# 1_P1.net
KiCad netlist of a schematic drawn in Altium Designer
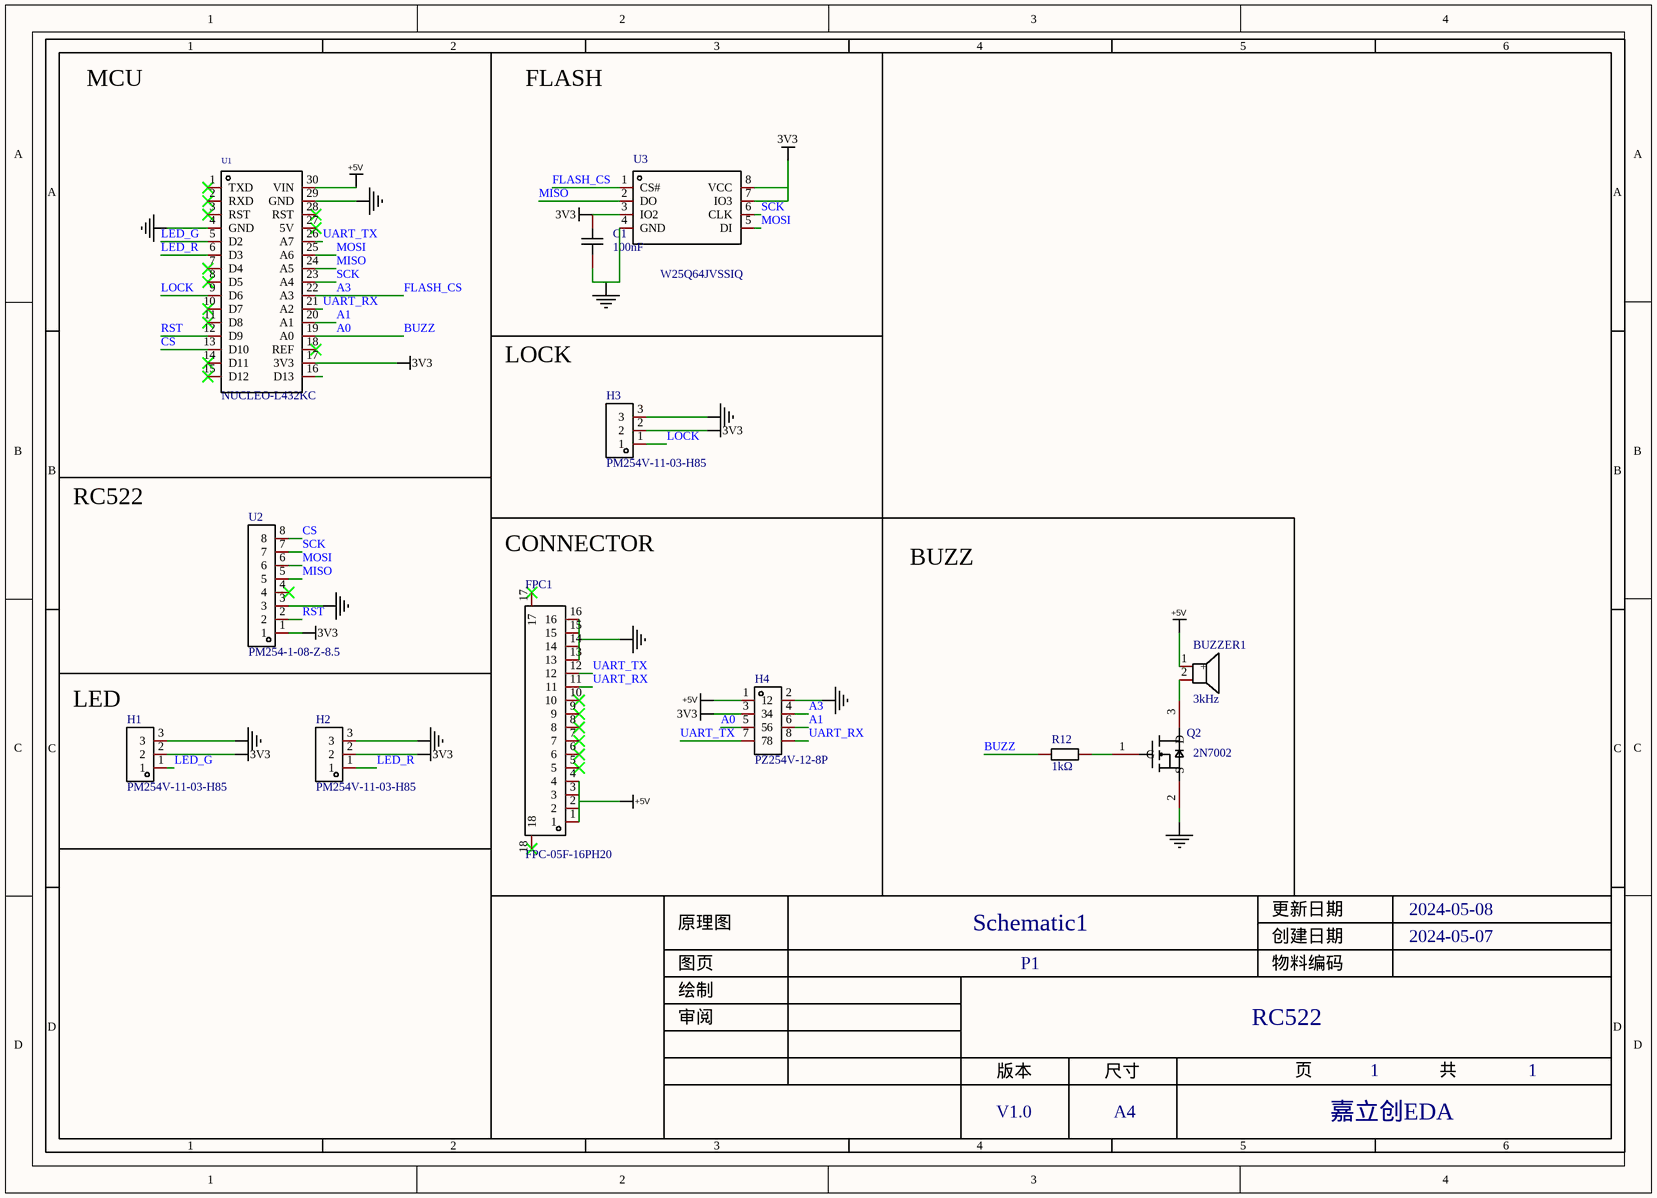
[diagram p0: 1_P1.schdoc]

(export (version "E")
  (design (tool "Eeschema 10.0.6"))
  (components
    (comp (ref "BUZZER1")
      (value "3kHz")
      (description "驱动方式:有源(内含驱动线路);构造类型:电磁式;频率:3kHz;声压(SPL):85dB@5V,10cm;")
      (fields
        (field (name "NAME") "3kHz")
        (field (name "MANUFACTURER") "华能")
        (field (name "MANUFACTURER PART") "HNB09A05")
      )
      (libsource (lib "altium-import") (part "root_0_HNB09A05_"))
    )
    (comp (ref "C1")
      (value "100nF")
      (description "容值:100nF;精度:±10%;额定电压:50V;材质(温度系数):X7R;")
      (fields
        (field (name "NAME") "100nF")
        (field (name "MANUFACTURER") "YAGEO(国巨)")
        (field (name "MANUFACTURER PART") "CC0603KRX7R9BB104")
      )
      (libsource (lib "altium-import") (part "root_1_CC0603KRX7R9BB104_"))
    )
    (comp (ref "FPC1")
      (value "FPC-05F-16PH20")
      (description "锁定特性:翻盖式;触点类型:下接;触点数量:16P;间距:0.5mm;安装类型:卧贴;工作温度范围:-25℃~+85℃;")
      (fields (field (name "NAME") "FPC-05F-16PH20") (field (name "MANUFACTURER") "XUNPU(讯普)"))
      (libsource (lib "altium-import") (part "root_2_FPC-05F-16PH20_"))
    )
    (comp (ref "H1")
      (value "PM254V-11-03-H85")
      (description "插孔结构:1x3P;间距:2.54mm;行距:-;安装类型:直插;排数:单排;总孔位数:3P;塑高:-;触头材质:黄铜;触头镀层:-;")
      (fields (field (name "NAME") "PM254V-11-03-H85") (field (name "MANUFACTURER") "XFCN(兴飞)"))
      (libsource (lib "altium-import") (part "root_2_PM254V-11-03-H85_"))
    )
    (comp (ref "H2")
      (value "PM254V-11-03-H85")
      (description "插孔结构:1x3P;间距:2.54mm;行距:-;安装类型:直插;排数:单排;总孔位数:3P;塑高:-;触头材质:黄铜;触头镀层:-;")
      (fields (field (name "NAME") "PM254V-11-03-H85") (field (name "MANUFACTURER") "XFCN(兴飞)"))
      (libsource (lib "altium-import") (part "root_2_PM254V-11-03-H85_"))
    )
    (comp (ref "H3")
      (value "PM254V-11-03-H85")
      (description "插孔结构:1x3P;间距:2.54mm;行距:-;安装类型:直插;排数:单排;总孔位数:3P;塑高:-;触头材质:黄铜;触头镀层:-;")
      (fields (field (name "NAME") "PM254V-11-03-H85") (field (name "MANUFACTURER") "XFCN(兴飞)"))
      (libsource (lib "altium-import") (part "root_2_PM254V-11-03-H85_"))
    )
    (comp (ref "H4")
      (value "PZ254V-12-8P")
      (fields (field (name "NAME") "PZ254V-12-8P") (field (name "MANUFACTURER") "XFCN(兴飞)"))
      (libsource (lib "altium-import") (part "root_0_PZ254V-12-8P_"))
    )
    (comp (ref "Q2")
      (value "2N7002")
      (fields (field (name "NAME") "2N7002") (field (name "MANUFACTURER") "JSMSEMI(杰盛微)"))
      (libsource (lib "altium-import") (part "root_0_2N7002_C916396_"))
    )
    (comp (ref "R12")
      (value "1kΩ")
      (description "电阻类型:厚膜电阻;阻值:1kΩ;精度:±1%;功率:100mW;最大工作电压:75V;温度系数:±100ppm/℃;")
      (fields
        (field (name "NAME") "1kΩ")
        (field (name "MANUFACTURER") "YAGEO(国巨)")
        (field (name "MANUFACTURER PART") "RC0603FR-071KL")
      )
      (libsource (lib "altium-import") (part "root_2_RC0603FR-071KL_"))
    )
    (comp (ref "U1")
      (value "NUCLEO-L432KC")
      (description "处理器:-;运行内存:-;USB:-;WIFI协议:-;蓝牙:-;以太网:-;")
      (fields (field (name "NAME") "NUCLEO-L432KC") (field (name "MANUFACTURER") "ST(意法半导体)"))
      (libsource (lib "altium-import") (part "root_0_NUCLEO-L432KC_"))
    )
    (comp (ref "U2")
      (value "PM254-1-08-Z-8.5")
      (fields (field (name "NAME") "PM254-1-08-Z-8.5") (field (name "MANUFACTURER") "HCTL(华灿天禄)"))
      (libsource (lib "altium-import") (part "root_2_PM254-1-08-Z-8.5_"))
    )
    (comp (ref "U3")
      (value "W25Q64JVSSIQ")
      (description "64M-bit/8M-byte FLASH芯片,SPI接口 133MHz(266/532MHz Dual/Quad-SPI) 比W25Q64FVSSIG更高速度")
      (fields (field (name "NAME") "W25Q64JVSSIQ") (field (name "MANUFACTURER") "WINBOND(华邦)"))
      (libsource (lib "altium-import") (part "root_0_W25Q64JVSSIQ_C83140_"))
    )
  )
  (nets
    (net (code "1") (name "+5V") (class "Default")
      (node (ref "BUZZER1") (pin "1") (pinfunction "+_1") (pintype "passive"))
      (node (ref "FPC1") (pin "1") (pinfunction "1_1") (pintype "passive"))
      (node (ref "FPC1") (pin "2") (pinfunction "2_2") (pintype "passive"))
      (node (ref "FPC1") (pin "3") (pinfunction "3_3") (pintype "passive"))
      (node (ref "FPC1") (pin "4") (pinfunction "4_4") (pintype "passive"))
      (node (ref "H4") (pin "1") (pinfunction "1_1") (pintype "passive"))
      (node (ref "U1") (pin "30") (pinfunction "VIN_30") (pintype "passive"))
    )
    (net (code "2") (name "/A0") (class "Default")
      (node (ref "H4") (pin "5") (pinfunction "5_5") (pintype "passive"))
      (node (ref "R12") (pin "2") (pinfunction "2_2") (pintype "passive"))
      (node (ref "U1") (pin "19") (pinfunction "A0_19") (pintype "passive"))
    )
    (net (code "3") (name "/A1") (class "Default")
      (node (ref "H4") (pin "6") (pinfunction "6_6") (pintype "passive"))
      (node (ref "U1") (pin "20") (pinfunction "A1_20") (pintype "passive"))
    )
    (net (code "4") (name "/A3") (class "Default")
      (node (ref "H4") (pin "4") (pinfunction "4_4") (pintype "passive"))
      (node (ref "U1") (pin "22") (pinfunction "A3_22") (pintype "passive"))
      (node (ref "U3") (pin "1") (pinfunction "CS#_1") (pintype "passive"))
    )
    (net (code "5") (name "/CS") (class "Default")
      (node (ref "U1") (pin "13") (pinfunction "D10_13") (pintype "passive"))
      (node (ref "U2") (pin "8") (pinfunction "8_8") (pintype "passive"))
    )
    (net (code "6") (name "/LED_G") (class "Default")
      (node (ref "H1") (pin "1") (pinfunction "1_1") (pintype "passive"))
      (node (ref "U1") (pin "5") (pinfunction "D2_5") (pintype "passive"))
    )
    (net (code "7") (name "/LED_R") (class "Default")
      (node (ref "H2") (pin "1") (pinfunction "1_1") (pintype "passive"))
      (node (ref "U1") (pin "6") (pinfunction "D3_6") (pintype "passive"))
    )
    (net (code "8") (name "/LOCK") (class "Default")
      (node (ref "H3") (pin "1") (pinfunction "1_1") (pintype "passive"))
      (node (ref "U1") (pin "9") (pinfunction "D6_9") (pintype "passive"))
    )
    (net (code "9") (name "/MISO") (class "Default")
      (node (ref "U1") (pin "24") (pinfunction "A5_24") (pintype "passive"))
      (node (ref "U2") (pin "5") (pinfunction "5_5") (pintype "passive"))
      (node (ref "U3") (pin "2") (pinfunction "DO_2") (pintype "passive"))
    )
    (net (code "10") (name "/MOSI") (class "Default")
      (node (ref "U1") (pin "25") (pinfunction "A6_25") (pintype "passive"))
      (node (ref "U2") (pin "6") (pinfunction "6_6") (pintype "passive"))
      (node (ref "U3") (pin "5") (pinfunction "DI_5") (pintype "passive"))
    )
    (net (code "11") (name "/RST") (class "Default")
      (node (ref "U1") (pin "12") (pinfunction "D9_12") (pintype "passive"))
      (node (ref "U2") (pin "2") (pinfunction "2_2") (pintype "passive"))
    )
    (net (code "12") (name "/SCK") (class "Default")
      (node (ref "U1") (pin "23") (pinfunction "A4_23") (pintype "passive"))
      (node (ref "U2") (pin "7") (pinfunction "7_7") (pintype "passive"))
      (node (ref "U3") (pin "6") (pinfunction "CLK_6") (pintype "passive"))
    )
    (net (code "13") (name "/UART_RX") (class "Default")
      (node (ref "FPC1") (pin "11") (pinfunction "11_11") (pintype "passive"))
      (node (ref "H4") (pin "8") (pinfunction "8_8") (pintype "passive"))
      (node (ref "U1") (pin "21") (pinfunction "A2_21") (pintype "passive"))
    )
    (net (code "14") (name "/UART_TX") (class "Default")
      (node (ref "FPC1") (pin "12") (pinfunction "12_12") (pintype "passive"))
      (node (ref "H4") (pin "7") (pinfunction "7_7") (pintype "passive"))
      (node (ref "U1") (pin "26") (pinfunction "A7_26") (pintype "passive"))
    )
    (net (code "15") (name "3V3") (class "Default")
      (node (ref "C1") (pin "2") (pinfunction "2_2") (pintype "passive"))
      (node (ref "H1") (pin "2") (pinfunction "2_2") (pintype "passive"))
      (node (ref "H2") (pin "2") (pinfunction "2_2") (pintype "passive"))
      (node (ref "H3") (pin "2") (pinfunction "2_2") (pintype "passive"))
      (node (ref "H4") (pin "3") (pinfunction "3_3") (pintype "passive"))
      (node (ref "U1") (pin "17") (pinfunction "3V3_17") (pintype "passive"))
      (node (ref "U2") (pin "1") (pinfunction "1_1") (pintype "passive"))
      (node (ref "U3") (pin "3") (pinfunction "IO2_3") (pintype "passive"))
      (node (ref "U3") (pin "7") (pinfunction "IO3_7") (pintype "passive"))
      (node (ref "U3") (pin "8") (pinfunction "VCC_8") (pintype "passive"))
    )
    (net (code "16") (name "<NO NET>") (class "Default")
      (node (ref "C1") (pin "1") (pinfunction "1_1") (pintype "passive"))
      (node (ref "FPC1") (pin "13") (pinfunction "13_13") (pintype "passive"))
      (node (ref "FPC1") (pin "14") (pinfunction "14_14") (pintype "passive"))
      (node (ref "FPC1") (pin "15") (pinfunction "15_15") (pintype "passive"))
      (node (ref "FPC1") (pin "16") (pinfunction "16_16") (pintype "passive"))
      (node (ref "H1") (pin "3") (pinfunction "3_3") (pintype "passive"))
      (node (ref "H2") (pin "3") (pinfunction "3_3") (pintype "passive"))
      (node (ref "H3") (pin "3") (pinfunction "3_3") (pintype "passive"))
      (node (ref "H4") (pin "2") (pinfunction "2_2") (pintype "passive"))
      (node (ref "Q2") (pin "2") (pinfunction "S_2") (pintype "passive"))
      (node (ref "U1") (pin "29") (pinfunction "GND_29") (pintype "passive"))
      (node (ref "U1") (pin "4") (pinfunction "GND_4") (pintype "passive"))
      (node (ref "U2") (pin "3") (pinfunction "3_3") (pintype "passive"))
      (node (ref "U3") (pin "4") (pinfunction "GND_4") (pintype "passive"))
    )
    (net (code "17") (name "Net-(Q2-D)") (class "Default")
      (node (ref "BUZZER1") (pin "2") (pinfunction "2_2") (pintype "passive"))
      (node (ref "Q2") (pin "3") (pinfunction "D_3") (pintype "passive"))
    )
    (net (code "18") (name "Net-(Q2-G)") (class "Default")
      (node (ref "Q2") (pin "1") (pinfunction "G_1") (pintype "passive"))
      (node (ref "R12") (pin "1") (pinfunction "1_1") (pintype "passive"))
    )
    (net (code "19") (name "unconnected-(FPC1-Pad5)") (class "Default")
      (node (ref "FPC1") (pin "5") (pinfunction "5_5") (pintype "passive+no_connect"))
    )
    (net (code "20") (name "unconnected-(FPC1-Pad6)") (class "Default")
      (node (ref "FPC1") (pin "6") (pinfunction "6_6") (pintype "passive+no_connect"))
    )
    (net (code "21") (name "unconnected-(FPC1-Pad7)") (class "Default")
      (node (ref "FPC1") (pin "7") (pinfunction "7_7") (pintype "passive+no_connect"))
    )
    (net (code "22") (name "unconnected-(FPC1-Pad8)") (class "Default")
      (node (ref "FPC1") (pin "8") (pinfunction "8_8") (pintype "passive+no_connect"))
    )
    (net (code "23") (name "unconnected-(FPC1-Pad9)") (class "Default")
      (node (ref "FPC1") (pin "9") (pinfunction "9_9") (pintype "passive+no_connect"))
    )
    (net (code "24") (name "unconnected-(FPC1-Pad10)") (class "Default")
      (node (ref "FPC1") (pin "10") (pinfunction "10_10") (pintype "passive+no_connect"))
    )
    (net (code "25") (name "unconnected-(FPC1-Pad17)") (class "Default")
      (node (ref "FPC1") (pin "17") (pinfunction "17_17") (pintype "passive+no_connect"))
    )
    (net (code "26") (name "unconnected-(FPC1-Pad18)") (class "Default")
      (node (ref "FPC1") (pin "18") (pinfunction "18_18") (pintype "passive+no_connect"))
    )
    (net (code "27") (name "unconnected-(U1-5V-Pad27)") (class "Default")
      (node (ref "U1") (pin "27") (pinfunction "5V_27") (pintype "passive+no_connect"))
    )
    (net (code "28") (name "unconnected-(U1-D4-Pad7)") (class "Default")
      (node (ref "U1") (pin "7") (pinfunction "D4_7") (pintype "passive+no_connect"))
    )
    (net (code "29") (name "unconnected-(U1-D5-Pad8)") (class "Default")
      (node (ref "U1") (pin "8") (pinfunction "D5_8") (pintype "passive+no_connect"))
    )
    (net (code "30") (name "unconnected-(U1-D7-Pad10)") (class "Default")
      (node (ref "U1") (pin "10") (pinfunction "D7_10") (pintype "passive+no_connect"))
    )
    (net (code "31") (name "unconnected-(U1-D8-Pad11)") (class "Default")
      (node (ref "U1") (pin "11") (pinfunction "D8_11") (pintype "passive+no_connect"))
    )
    (net (code "32") (name "unconnected-(U1-D11-Pad14)") (class "Default")
      (node (ref "U1") (pin "14") (pinfunction "D11_14") (pintype "passive+no_connect"))
    )
    (net (code "33") (name "unconnected-(U1-D12-Pad15)") (class "Default")
      (node (ref "U1") (pin "15") (pinfunction "D12_15") (pintype "passive+no_connect"))
    )
    (net (code "34") (name "unconnected-(U1-D13-Pad16)") (class "Default")
      (node (ref "U1") (pin "16") (pinfunction "D13_16") (pintype "passive"))
    )
    (net (code "35") (name "unconnected-(U1-REF-Pad18)") (class "Default")
      (node (ref "U1") (pin "18") (pinfunction "REF_18") (pintype "passive+no_connect"))
    )
    (net (code "36") (name "unconnected-(U1-RST-Pad3)") (class "Default")
      (node (ref "U1") (pin "3") (pinfunction "RST_3") (pintype "passive+no_connect"))
    )
    (net (code "37") (name "unconnected-(U1-RST-Pad28)") (class "Default")
      (node (ref "U1") (pin "28") (pinfunction "RST_28") (pintype "passive+no_connect"))
    )
    (net (code "38") (name "unconnected-(U1-RXD-Pad2)") (class "Default")
      (node (ref "U1") (pin "2") (pinfunction "RXD_2") (pintype "passive+no_connect"))
    )
    (net (code "39") (name "unconnected-(U1-TXD-Pad1)") (class "Default")
      (node (ref "U1") (pin "1") (pinfunction "TXD_1") (pintype "passive+no_connect"))
    )
    (net (code "40") (name "unconnected-(U2-Pad4)") (class "Default")
      (node (ref "U2") (pin "4") (pinfunction "4_4") (pintype "passive+no_connect"))
    )
  )
)
